# 04-.net
KiCad netlist of a schematic drawn in Altium Designer
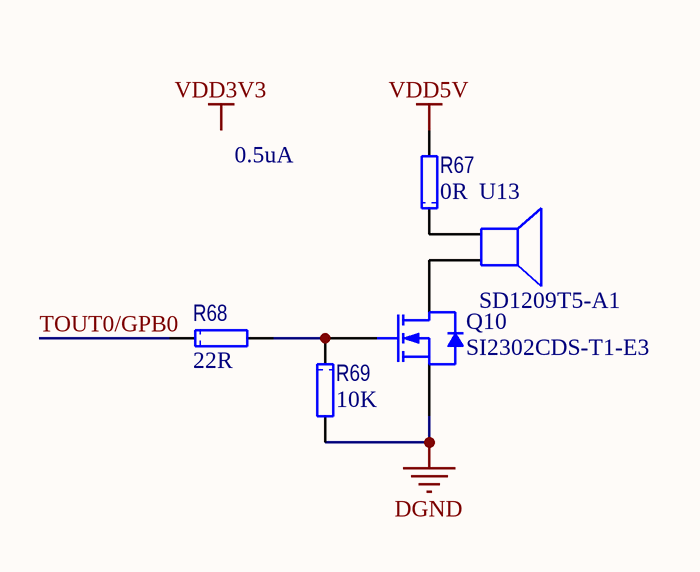
[diagram p0: 04-蜂鸣器.SchDoc]

(export (version "E")
  (design (tool "Eeschema 10.0.6"))
  (components
    (comp (ref "Q10")
      (value "SI2302CDS-T1-E3")
      (footprint "SOT23_N")
      (description "MOSFET 20V 2.9A 0.86W 57mohm @ 4.5V")
      (fields (field (name "MANUFACTURER") "Vishay / Siliconix"))
      (libsource (lib "Philips Discrete MOSFET - Low Power") (part "2N7002"))
    )
    (comp (ref "R67")
      (value "0R")
      (footprint "1608[0603]R")
      (description "厚膜电阻器 - SMD 1/10watt ZEROohm Jumper")
      (fields
        (field (name "MANUFACTURER") "Vishay / Dale")
        (field (name "MANUFACTURER PART NUMBER") "CRCW06030000ZSTA")
      )
      (libsource (lib "0R 1%") (part "RES"))
    )
    (comp (ref "R68")
      (value "22R")
      (footprint "1608[0603]R")
      (description "厚膜电阻器 - SMD 1/10watt 22ohms 1%")
      (fields
        (field (name "MANUFACTURER") "Vishay / Dale")
        (field (name "MANUFACTURER PART NUMBER") "CRCW060322R0FKEA")
      )
      (libsource (lib "22R 1%") (part "RES"))
    )
    (comp (ref "R69")
      (value "10K")
      (footprint "1608[0603]R")
      (description "厚膜电阻器 - SMD 1/10watt 10Kohms 1%")
      (fields
        (field (name "MANUFACTURER") "Vishay / Dale")
        (field (name "MANUFACTURER PART NUMBER") "CRCW060310K0FKEA")
      )
      (libsource (lib "10K 1%") (part "RES"))
    )
    (comp (ref "U13")
      (value "SD1209T5-A1")
      (footprint "Speaker")
      (description "插针 BUZZER MAGNET 2048HZ 12MM PC MNT")
      (fields
        (field (name "MANUFACTURER") "TDK Corporation")
        (field (name "MANUFACTURER PART NUMBER") "SD1209T3-A1")
      )
      (libsource (lib "*") (part "SPEAKER"))
    )
  )
  (nets
    (net (code "1") (name "/TOUT0{slash}GPB0") (class "Default")
      (node (ref "R68") (pin "1") (pinfunction "1_1") (pintype "passive"))
    )
    (net (code "2") (name "DGND") (class "Default")
      (node (ref "Q10") (pin "2") (pinfunction "S_2") (pintype "passive"))
      (node (ref "R69") (pin "2") (pinfunction "2_2") (pintype "passive"))
    )
    (net (code "3") (name "Net-(Q10-D)") (class "Default")
      (node (ref "Q10") (pin "3") (pinfunction "D_3") (pintype "passive"))
      (node (ref "U13") (pin "2") (pinfunction "2_2") (pintype "passive"))
    )
    (net (code "4") (name "Net-(Q10-G)") (class "Default")
      (node (ref "Q10") (pin "1") (pinfunction "G_1") (pintype "passive"))
      (node (ref "R68") (pin "2") (pinfunction "2_2") (pintype "passive"))
      (node (ref "R69") (pin "1") (pinfunction "1_1") (pintype "passive"))
    )
    (net (code "5") (name "Net-(R67-Pad1)") (class "Default")
      (node (ref "R67") (pin "1") (pinfunction "1_1") (pintype "passive"))
      (node (ref "U13") (pin "1") (pinfunction "1_1") (pintype "passive"))
    )
    (net (code "7") (name "VDD5V") (class "Default")
      (node (ref "R67") (pin "2") (pinfunction "2_2") (pintype "passive"))
    )
  )
)
